# Sheet_connectors.net
KiCad netlist of a schematic drawn in Altium Designer
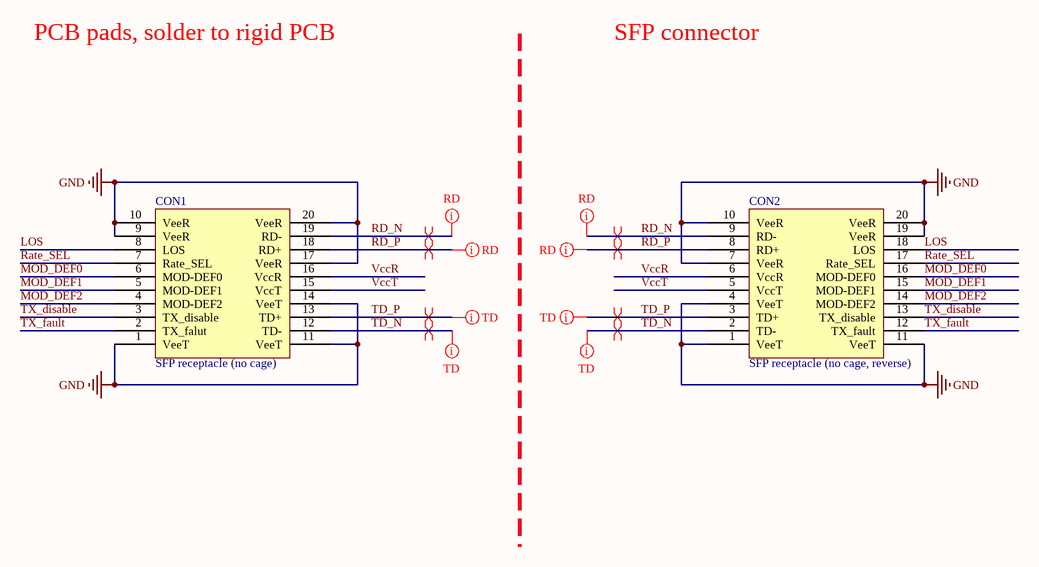
[diagram p0: Sheet_connectors.SchDoc]

(export (version "E")
  (design (tool "Eeschema 10.0.6"))
  (components
    (comp (ref "CON1")
      (value "SFP receptacle (no cage)")
      (footprint "SFP PCB CON")
      (description "SFP receptacle, woutout cage, standard orientation of SFP module")
      (libsource (lib "Connectors") (part "SFP connector"))
    )
    (comp (ref "CON2")
      (value "SFP receptacle (no cage, reverse)")
      (footprint "SFP receptacle (no cage)")
      (description "SFP receptacle, woutout cage, reverse orientation of SFP module")
      (libsource (lib "Connectors") (part "SFP connector reverse"))
    )
  )
  (nets
    (net (code "1") (name "/LOS") (class "Default")
      (node (ref "CON1") (pin "8") (pinfunction "LOS_8") (pintype "passive"))
      (node (ref "CON2") (pin "18") (pinfunction "LOS_18") (pintype "passive"))
    )
    (net (code "2") (name "/MOD_DEF0") (class "Default")
      (node (ref "CON1") (pin "6") (pinfunction "MOD-DEF0_6") (pintype "passive"))
      (node (ref "CON2") (pin "16") (pinfunction "MOD-DEF0_16") (pintype "passive"))
    )
    (net (code "3") (name "/MOD_DEF1") (class "Default")
      (node (ref "CON1") (pin "5") (pinfunction "MOD-DEF1_5") (pintype "passive"))
      (node (ref "CON2") (pin "15") (pinfunction "MOD-DEF1_15") (pintype "passive"))
    )
    (net (code "4") (name "/MOD_DEF2") (class "Default")
      (node (ref "CON1") (pin "4") (pinfunction "MOD-DEF2_4") (pintype "passive"))
      (node (ref "CON2") (pin "14") (pinfunction "MOD-DEF2_14") (pintype "passive"))
    )
    (net (code "5") (name "/RD_N") (class "Default")
      (node (ref "CON1") (pin "19") (pinfunction "RD-_19") (pintype "passive"))
      (node (ref "CON2") (pin "9") (pinfunction "RD-_9") (pintype "passive"))
    )
    (net (code "6") (name "/RD_P") (class "Default")
      (node (ref "CON1") (pin "18") (pinfunction "RD+_18") (pintype "passive"))
      (node (ref "CON2") (pin "8") (pinfunction "RD+_8") (pintype "passive"))
    )
    (net (code "7") (name "/Rate_SEL") (class "Default")
      (node (ref "CON1") (pin "7") (pinfunction "Rate_SEL_7") (pintype "passive"))
      (node (ref "CON2") (pin "17") (pinfunction "Rate_SEL_17") (pintype "passive"))
    )
    (net (code "8") (name "/TD_N") (class "Default")
      (node (ref "CON1") (pin "12") (pinfunction "TD-_12") (pintype "passive"))
      (node (ref "CON2") (pin "2") (pinfunction "TD-_2") (pintype "passive"))
    )
    (net (code "9") (name "/TD_P") (class "Default")
      (node (ref "CON1") (pin "13") (pinfunction "TD+_13") (pintype "passive"))
      (node (ref "CON2") (pin "3") (pinfunction "TD+_3") (pintype "passive"))
    )
    (net (code "10") (name "/TX_disable") (class "Default")
      (node (ref "CON1") (pin "3") (pinfunction "TX_disable_3") (pintype "passive"))
      (node (ref "CON2") (pin "13") (pinfunction "TX_disable_13") (pintype "passive"))
    )
    (net (code "11") (name "/TX_fault") (class "Default")
      (node (ref "CON1") (pin "2") (pinfunction "TX_falut_2") (pintype "passive"))
      (node (ref "CON2") (pin "12") (pinfunction "TX_fault_12") (pintype "passive"))
    )
    (net (code "12") (name "/VccR") (class "Default")
      (node (ref "CON1") (pin "16") (pinfunction "VccR_16") (pintype "passive"))
      (node (ref "CON2") (pin "6") (pinfunction "VccR_6") (pintype "passive"))
    )
    (net (code "13") (name "/VccT") (class "Default")
      (node (ref "CON1") (pin "15") (pinfunction "VccT_15") (pintype "passive"))
      (node (ref "CON2") (pin "5") (pinfunction "VccT_5") (pintype "passive"))
    )
    (net (code "14") (name "GND") (class "Default")
      (node (ref "CON1") (pin "1") (pinfunction "VeeT_1") (pintype "passive"))
      (node (ref "CON1") (pin "10") (pinfunction "VeeR_10") (pintype "passive"))
      (node (ref "CON1") (pin "11") (pinfunction "VeeT_11") (pintype "passive"))
      (node (ref "CON1") (pin "14") (pinfunction "VeeT_14") (pintype "passive"))
      (node (ref "CON1") (pin "17") (pinfunction "VeeR_17") (pintype "passive"))
      (node (ref "CON1") (pin "20") (pinfunction "VeeR_20") (pintype "passive"))
      (node (ref "CON1") (pin "9") (pinfunction "VeeR_9") (pintype "passive"))
      (node (ref "CON2") (pin "1") (pinfunction "VeeT_1") (pintype "passive"))
      (node (ref "CON2") (pin "10") (pinfunction "VeeR_10") (pintype "passive"))
      (node (ref "CON2") (pin "11") (pinfunction "VeeT_11") (pintype "passive"))
      (node (ref "CON2") (pin "19") (pinfunction "VeeR_19") (pintype "passive"))
      (node (ref "CON2") (pin "20") (pinfunction "VeeR_20") (pintype "passive"))
      (node (ref "CON2") (pin "4") (pinfunction "VeeT_4") (pintype "passive"))
      (node (ref "CON2") (pin "7") (pinfunction "VeeR_7") (pintype "passive"))
    )
  )
)
